# SCH_ESP32_Master_Board_2023-08-22.net
KiCad netlist of a schematic drawn in EasyEDA
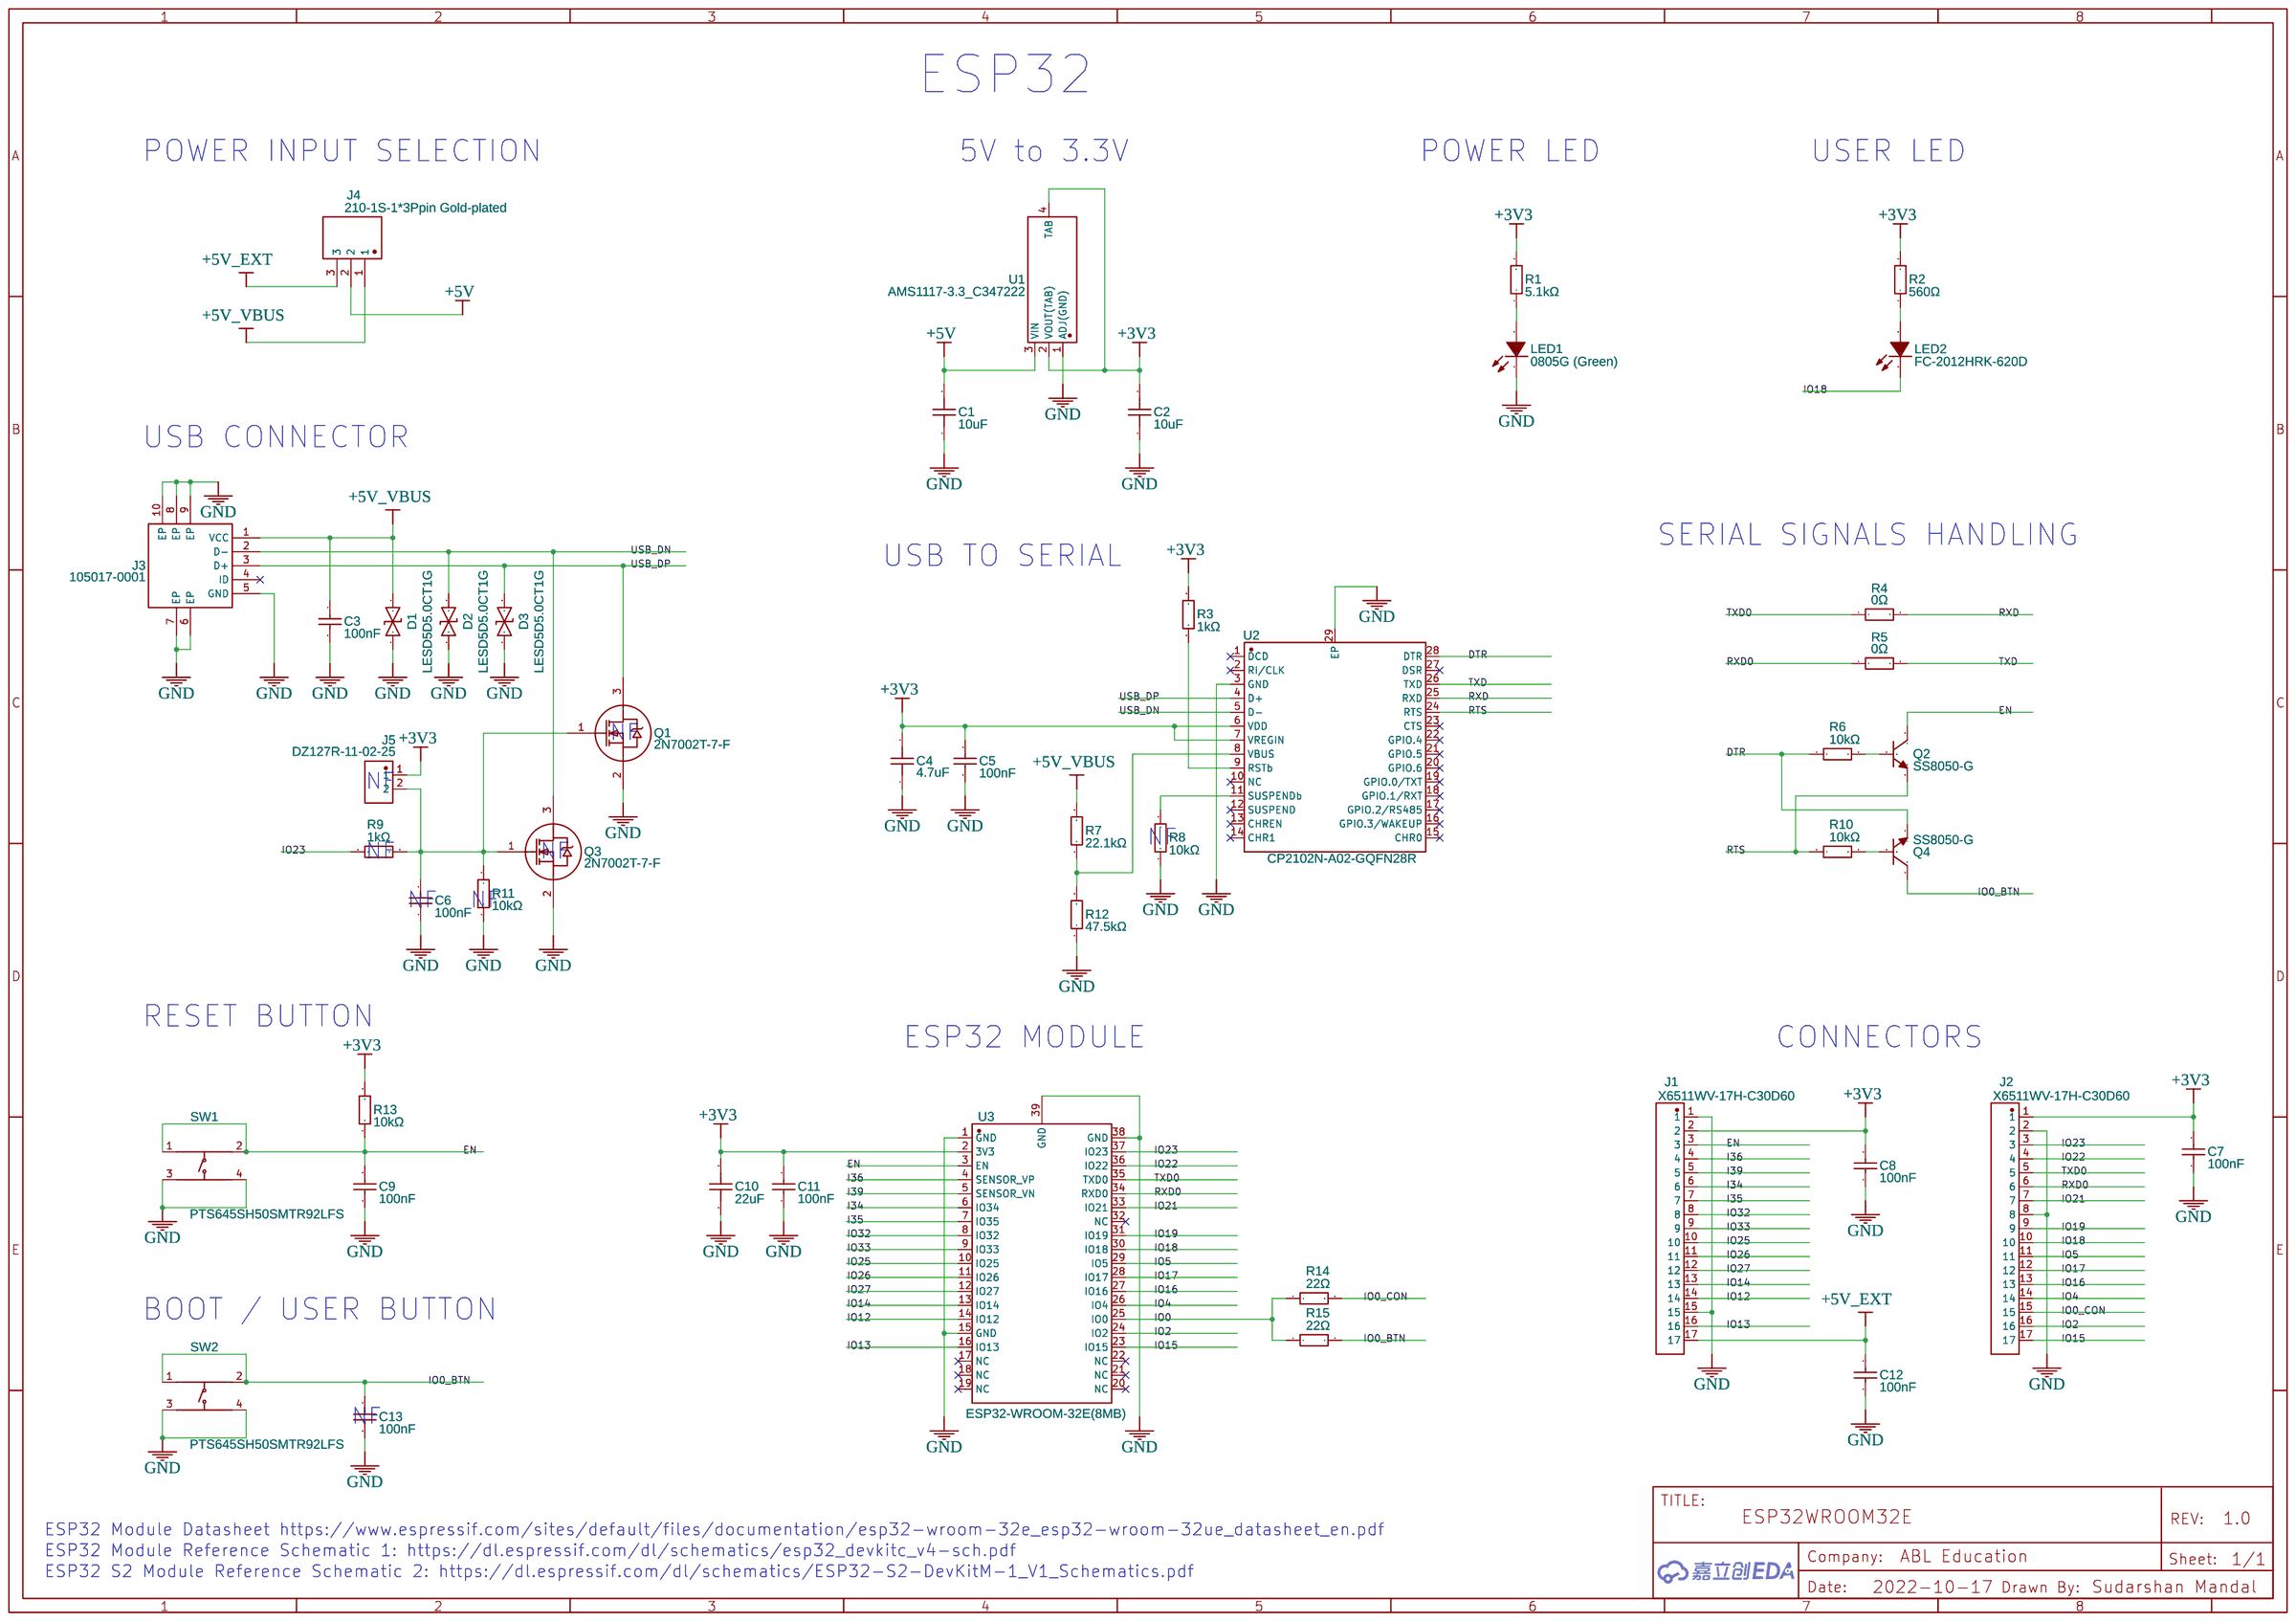
[diagram p0: schematic sheet]

(export (version "E")
  (design (tool "Eeschema 10.0.6"))
  (components
    (comp (ref "C1")
      (value "10uF")
      (fields
        (field (name "Manufacturer Part") "CL05A106MP5NUNC")
        (field (name "Manufacturer") "Samsung Electro-Mechanics")
      )
      (libsource (lib "") (part "CL05A106MP5NUNC_C315248"))
    )
    (comp (ref "C2")
      (value "10uF")
      (fields
        (field (name "Manufacturer Part") "CL05A106MP5NUNC")
        (field (name "Manufacturer") "Samsung Electro-Mechanics")
      )
      (libsource (lib "") (part "CL05A106MP5NUNC_C315248"))
    )
    (comp (ref "C3")
      (value "100nF")
      (fields (field (name "Manufacturer Part") "CL05B104KO5NNNC") (field (name "Manufacturer") "SAMSUNG"))
      (libsource (lib "") (part "CL05B104KO5NNNC"))
    )
    (comp (ref "C4")
      (value "4.7uF")
      (fields
        (field (name "Manufacturer Part") "CL05A475KP5NRNC")
        (field (name "Manufacturer") "Samsung Electro-Mechanics")
      )
      (libsource (lib "") (part "CL05A475KP5NRNC"))
    )
    (comp (ref "C5")
      (value "100nF")
      (fields (field (name "Manufacturer Part") "CL05B104KO5NNNC") (field (name "Manufacturer") "SAMSUNG"))
      (libsource (lib "") (part "CL05B104KO5NNNC"))
    )
    (comp (ref "C6")
      (value "100nF")
      (fields (field (name "Manufacturer Part") "CL05B104KO5NNNC") (field (name "Manufacturer") "SAMSUNG"))
      (libsource (lib "") (part "CL05B104KO5NNNC"))
    )
    (comp (ref "C7")
      (value "100nF")
      (fields (field (name "Manufacturer Part") "CL05B104KO5NNNC") (field (name "Manufacturer") "SAMSUNG"))
      (libsource (lib "") (part "CL05B104KO5NNNC"))
    )
    (comp (ref "C8")
      (value "100nF")
      (fields (field (name "Manufacturer Part") "CL05B104KO5NNNC") (field (name "Manufacturer") "SAMSUNG"))
      (libsource (lib "") (part "CL05B104KO5NNNC"))
    )
    (comp (ref "C9")
      (value "100nF")
      (fields (field (name "Manufacturer Part") "CL05B104KO5NNNC") (field (name "Manufacturer") "SAMSUNG"))
      (libsource (lib "") (part "CL05B104KO5NNNC"))
    )
    (comp (ref "C10")
      (value "22uF")
      (fields
        (field (name "Manufacturer Part") "CL21A226MAYNNNE")
        (field (name "Manufacturer") "Samsung Electro-Mechanics")
      )
      (libsource (lib "") (part "CL21A226MAYNNNE"))
    )
    (comp (ref "C11")
      (value "100nF")
      (fields (field (name "Manufacturer Part") "CL05B104KO5NNNC") (field (name "Manufacturer") "SAMSUNG"))
      (libsource (lib "") (part "CL05B104KO5NNNC"))
    )
    (comp (ref "C12")
      (value "100nF")
      (fields (field (name "Manufacturer Part") "CL05B104KO5NNNC") (field (name "Manufacturer") "SAMSUNG"))
      (libsource (lib "") (part "CL05B104KO5NNNC"))
    )
    (comp (ref "C13")
      (value "100nF")
      (fields (field (name "Manufacturer Part") "CL05B104KO5NNNC") (field (name "Manufacturer") "SAMSUNG"))
      (libsource (lib "") (part "CL05B104KO5NNNC"))
    )
    (comp (ref "D1")
      (value "LESD5D5.0CT1G")
      (fields (field (name "Manufacturer") "Leshan Radio"))
      (libsource (lib "") (part "LESD5D5.0CT1G"))
    )
    (comp (ref "D2")
      (value "LESD5D5.0CT1G")
      (fields (field (name "Manufacturer") "Leshan Radio"))
      (libsource (lib "") (part "LESD5D5.0CT1G"))
    )
    (comp (ref "D3")
      (value "LESD5D5.0CT1G")
      (fields (field (name "Manufacturer") "Leshan Radio"))
      (libsource (lib "") (part "LESD5D5.0CT1G"))
    )
    (comp (ref "J1")
      (value "X6511WV-17H-C30D60")
      (fields (field (name "Manufacturer") "XKB Connectivity"))
      (libsource (lib "") (part "X6511WV-17H-C30D60"))
    )
    (comp (ref "J2")
      (value "X6511WV-17H-C30D60")
      (fields (field (name "Manufacturer") "XKB Connectivity"))
      (libsource (lib "") (part "X6511WV-17H-C30D60"))
    )
    (comp (ref "J3")
      (value "105017-0001")
      (fields (field (name "Manufacturer") "MOLEX"))
      (libsource (lib "") (part "105017-0001"))
    )
    (comp (ref "J4")
      (value "210-1S-1*3Ppin Gold-plated")
      (fields (field (name "Manufacturer") "Ckmtw"))
      (libsource (lib "") (part "210-1S-1*3Ppin Gold-plated"))
    )
    (comp (ref "J5")
      (value "DZ127R-11-02-25")
      (fields (field (name "Manufacturer") "DEALON(德艺隆)"))
      (libsource (lib "") (part "DZ127R-11-02-25"))
    )
    (comp (ref "LED1")
      (value "0805G (Green)")
      (fields (field (name "Manufacturer") "KENTO"))
      (libsource (lib "") (part "0805G (Green)"))
    )
    (comp (ref "LED2")
      (value "FC-2012HRK-620D")
      (fields (field (name "Manufacturer") "NATIONSTAR"))
      (libsource (lib "") (part "FC-2012HRK-620D"))
    )
    (comp (ref "Q1")
      (value "2N7002T-7-F")
      (fields (field (name "Manufacturer") "DIODES"))
      (libsource (lib "") (part "2N7002T-7-F"))
    )
    (comp (ref "Q2")
      (value "SS8050-G")
      (fields (field (name "Manufacturer") "CJ(江苏长电/长晶)"))
      (libsource (lib "") (part "SS8050-G"))
    )
    (comp (ref "Q3")
      (value "2N7002T-7-F")
      (fields (field (name "Manufacturer") "DIODES"))
      (libsource (lib "") (part "2N7002T-7-F"))
    )
    (comp (ref "Q4")
      (value "SS8050-G")
      (fields (field (name "Manufacturer") "CJ(江苏长电/长晶)"))
      (libsource (lib "") (part "SS8050-G_1"))
    )
    (comp (ref "R1")
      (value "5.1kΩ")
      (fields (field (name "Manufacturer Part") "0402WGF5101TCE") (field (name "Manufacturer") "UniOhm"))
      (libsource (lib "") (part "0402WGF5101TCE"))
    )
    (comp (ref "R2")
      (value "560Ω")
      (fields (field (name "Manufacturer Part") "0402WGF5600TCE") (field (name "Manufacturer") "UniOhm"))
      (libsource (lib "") (part "0402WGF5600TCE"))
    )
    (comp (ref "R3")
      (value "1kΩ")
      (fields (field (name "Manufacturer Part") "0402WGF1001TCE") (field (name "Manufacturer") "UniOhm"))
      (libsource (lib "") (part "0402WGF1001TCE"))
    )
    (comp (ref "R4")
      (value "0Ω")
      (fields (field (name "Manufacturer Part") "0402WGF0000TCE") (field (name "Manufacturer") "UniOhm"))
      (libsource (lib "") (part "0402WGF0000TCE"))
    )
    (comp (ref "R5")
      (value "0Ω")
      (fields (field (name "Manufacturer Part") "0402WGF0000TCE") (field (name "Manufacturer") "UniOhm"))
      (libsource (lib "") (part "0402WGF0000TCE"))
    )
    (comp (ref "R6")
      (value "10kΩ")
      (fields (field (name "Manufacturer Part") "0402WGF1002TCE") (field (name "Manufacturer") "UniOhm"))
      (libsource (lib "") (part "0402WGF1002TCE_1"))
    )
    (comp (ref "R7")
      (value "22.1kΩ")
      (fields (field (name "Manufacturer Part") "0402WGF2212TCE") (field (name "Manufacturer") "UniOhm"))
      (libsource (lib "") (part "0402WGF2212TCE"))
    )
    (comp (ref "R8")
      (value "10kΩ")
      (fields (field (name "Manufacturer Part") "0402WGF1002TCE") (field (name "Manufacturer") "UniOhm"))
      (libsource (lib "") (part "0402WGF1002TCE"))
    )
    (comp (ref "R9")
      (value "1kΩ")
      (fields (field (name "Manufacturer Part") "0402WGF1001TCE") (field (name "Manufacturer") "UniOhm"))
      (libsource (lib "") (part "0402WGF1001TCE_1"))
    )
    (comp (ref "R10")
      (value "10kΩ")
      (fields (field (name "Manufacturer Part") "0402WGF1002TCE") (field (name "Manufacturer") "UniOhm"))
      (libsource (lib "") (part "0402WGF1002TCE_1"))
    )
    (comp (ref "R11")
      (value "10kΩ")
      (fields (field (name "Manufacturer Part") "0402WGF1002TCE") (field (name "Manufacturer") "UniOhm"))
      (libsource (lib "") (part "0402WGF1002TCE"))
    )
    (comp (ref "R12")
      (value "47.5kΩ")
      (fields (field (name "Manufacturer Part") "0402WGF4752TCE") (field (name "Manufacturer") "UniOhm"))
      (libsource (lib "") (part "0402WGF4752TCE"))
    )
    (comp (ref "R13")
      (value "10kΩ")
      (fields (field (name "Manufacturer Part") "0402WGF1002TCE") (field (name "Manufacturer") "UniOhm"))
      (libsource (lib "") (part "0402WGF1002TCE"))
    )
    (comp (ref "R14")
      (value "22Ω")
      (fields (field (name "Manufacturer Part") "0402WGF220JTCE") (field (name "Manufacturer") "UniOhm"))
      (libsource (lib "") (part "0402WGF220JTCE"))
    )
    (comp (ref "R15")
      (value "22Ω")
      (fields (field (name "Manufacturer Part") "0402WGF220JTCE") (field (name "Manufacturer") "UniOhm"))
      (libsource (lib "") (part "0402WGF220JTCE"))
    )
    (comp (ref "SW1")
      (value "PTS645SH50SMTR92LFS")
      (fields (field (name "Manufacturer") "C&K"))
      (libsource (lib "") (part "PTS645SH50SMTR92LFS"))
    )
    (comp (ref "SW2")
      (value "PTS645SH50SMTR92LFS")
      (fields (field (name "Manufacturer") "C&K"))
      (libsource (lib "") (part "PTS645SH50SMTR92LFS"))
    )
    (comp (ref "U1")
      (value "AMS1117-3.3_C347222")
      (fields
        (field (name "Manufacturer Part") "AMS1117-3.3")
        (field (name "Manufacturer") "Youtai Semiconductor Co., Ltd.")
      )
      (libsource (lib "") (part "AMS1117-3.3_C347222"))
    )
    (comp (ref "U2")
      (value "CP2102N-A02-GQFN28R")
      (fields (field (name "Manufacturer") "SILICON LABS(芯科)"))
      (libsource (lib "") (part "CP2102N-A02-GQFN28R"))
    )
    (comp (ref "U3")
      (value "ESP32-WROOM-32E(8MB)")
      (fields (field (name "Manufacturer") "Espressif Systems"))
      (libsource (lib "") (part "ESP32-WROOM-32E(8MB)"))
    )
  )
  (nets
    (net (code "1") (name "+3V3") (class "Default")
      (node (ref "C10") (pin "2") (pinfunction "2_2") (pintype "unspecified"))
      (node (ref "C11") (pin "2") (pinfunction "2_2") (pintype "input"))
      (node (ref "C2") (pin "2") (pinfunction "2_2") (pintype "unspecified"))
      (node (ref "C4") (pin "2") (pinfunction "2_2") (pintype "unspecified"))
      (node (ref "C5") (pin "2") (pinfunction "2_2") (pintype "input"))
      (node (ref "C7") (pin "2") (pinfunction "2_2") (pintype "input"))
      (node (ref "C8") (pin "2") (pinfunction "2_2") (pintype "input"))
      (node (ref "J1") (pin "2") (pinfunction "2_2") (pintype "unspecified"))
      (node (ref "J2") (pin "1") (pinfunction "1_1") (pintype "unspecified"))
      (node (ref "J5") (pin "1") (pinfunction "1_1") (pintype "unspecified"))
      (node (ref "R1") (pin "2") (pinfunction "2_2") (pintype "input"))
      (node (ref "R13") (pin "2") (pinfunction "2_2") (pintype "input"))
      (node (ref "R2") (pin "2") (pinfunction "2_2") (pintype "input"))
      (node (ref "R3") (pin "2") (pinfunction "2_2") (pintype "input"))
      (node (ref "U1") (pin "2") (pinfunction "VOUT(TAB)_2") (pintype "unspecified"))
      (node (ref "U1") (pin "4") (pinfunction "TAB_4") (pintype "unspecified"))
      (node (ref "U2") (pin "6") (pinfunction "VDD_6") (pintype "unspecified"))
      (node (ref "U2") (pin "7") (pinfunction "VREGIN_7") (pintype "unspecified"))
      (node (ref "U3") (pin "2") (pinfunction "3V3_2") (pintype "unspecified"))
    )
    (net (code "2") (name "+5V") (class "Default")
      (node (ref "C1") (pin "2") (pinfunction "2_2") (pintype "unspecified"))
      (node (ref "J4") (pin "2") (pinfunction "2_2") (pintype "unspecified"))
      (node (ref "U1") (pin "3") (pinfunction "VIN_3") (pintype "unspecified"))
    )
    (net (code "3") (name "+5V_EXT") (class "Default")
      (node (ref "C12") (pin "2") (pinfunction "2_2") (pintype "input"))
      (node (ref "J1") (pin "17") (pinfunction "17_17") (pintype "unspecified"))
      (node (ref "J4") (pin "3") (pinfunction "3_3") (pintype "unspecified"))
    )
    (net (code "4") (name "+5V_VBUS") (class "Default")
      (node (ref "C3") (pin "2") (pinfunction "2_2") (pintype "input"))
      (node (ref "D1") (pin "2") (pinfunction "2_2") (pintype "unspecified"))
      (node (ref "J3") (pin "1") (pinfunction "VCC_1") (pintype "unspecified"))
      (node (ref "J4") (pin "1") (pinfunction "1_1") (pintype "unspecified"))
      (node (ref "R7") (pin "2") (pinfunction "2_2") (pintype "input"))
    )
    (net (code "5") (name "/DTR") (class "Default")
      (node (ref "Q4") (pin "2") (pinfunction "E_2") (pintype "input"))
      (node (ref "R6") (pin "1") (pinfunction "1_1") (pintype "input"))
      (node (ref "U2") (pin "28") (pinfunction "DTR_28") (pintype "unspecified"))
    )
    (net (code "6") (name "/EN") (class "Default")
      (node (ref "C9") (pin "2") (pinfunction "2_2") (pintype "input"))
      (node (ref "J1") (pin "3") (pinfunction "3_3") (pintype "unspecified"))
      (node (ref "Q2") (pin "3") (pinfunction "C_3") (pintype "input"))
      (node (ref "R13") (pin "1") (pinfunction "1_1") (pintype "input"))
      (node (ref "SW1") (pin "1") (pinfunction "1_1") (pintype "unspecified"))
      (node (ref "SW1") (pin "2") (pinfunction "2_2") (pintype "unspecified"))
      (node (ref "U3") (pin "3") (pinfunction "EN_3") (pintype "unspecified"))
    )
    (net (code "7") (name "/I34") (class "Default")
      (node (ref "J1") (pin "6") (pinfunction "6_6") (pintype "unspecified"))
      (node (ref "U3") (pin "6") (pinfunction "IO34_6") (pintype "unspecified"))
    )
    (net (code "8") (name "/I35") (class "Default")
      (node (ref "J1") (pin "7") (pinfunction "7_7") (pintype "unspecified"))
      (node (ref "U3") (pin "7") (pinfunction "IO35_7") (pintype "unspecified"))
    )
    (net (code "9") (name "/I36") (class "Default")
      (node (ref "J1") (pin "4") (pinfunction "4_4") (pintype "unspecified"))
      (node (ref "U3") (pin "4") (pinfunction "SENSOR_VP_4") (pintype "unspecified"))
    )
    (net (code "10") (name "/I39") (class "Default")
      (node (ref "J1") (pin "5") (pinfunction "5_5") (pintype "unspecified"))
      (node (ref "U3") (pin "5") (pinfunction "SENSOR_VN_5") (pintype "unspecified"))
    )
    (net (code "11") (name "/IO0") (class "Default")
      (node (ref "R14") (pin "1") (pinfunction "1_1") (pintype "input"))
      (node (ref "R15") (pin "1") (pinfunction "1_1") (pintype "input"))
      (node (ref "U3") (pin "25") (pinfunction "IO0_25") (pintype "unspecified"))
    )
    (net (code "12") (name "/IO0_BTN") (class "Default")
      (node (ref "C13") (pin "2") (pinfunction "2_2") (pintype "input"))
      (node (ref "Q4") (pin "3") (pinfunction "C_3") (pintype "input"))
      (node (ref "R15") (pin "2") (pinfunction "2_2") (pintype "input"))
      (node (ref "SW2") (pin "1") (pinfunction "1_1") (pintype "unspecified"))
      (node (ref "SW2") (pin "2") (pinfunction "2_2") (pintype "unspecified"))
    )
    (net (code "13") (name "/IO0_CON") (class "Default")
      (node (ref "J2") (pin "15") (pinfunction "15_15") (pintype "unspecified"))
      (node (ref "R14") (pin "2") (pinfunction "2_2") (pintype "input"))
    )
    (net (code "14") (name "/IO2") (class "Default")
      (node (ref "J2") (pin "16") (pinfunction "16_16") (pintype "unspecified"))
      (node (ref "U3") (pin "24") (pinfunction "IO2_24") (pintype "unspecified"))
    )
    (net (code "15") (name "/IO4") (class "Default")
      (node (ref "J2") (pin "14") (pinfunction "14_14") (pintype "unspecified"))
      (node (ref "U3") (pin "26") (pinfunction "IO4_26") (pintype "unspecified"))
    )
    (net (code "16") (name "/IO5") (class "Default")
      (node (ref "J2") (pin "11") (pinfunction "11_11") (pintype "unspecified"))
      (node (ref "U3") (pin "29") (pinfunction "IO5_29") (pintype "unspecified"))
    )
    (net (code "17") (name "/IO12") (class "Default")
      (node (ref "J1") (pin "14") (pinfunction "14_14") (pintype "unspecified"))
      (node (ref "U3") (pin "14") (pinfunction "IO12_14") (pintype "unspecified"))
    )
    (net (code "18") (name "/IO13") (class "Default")
      (node (ref "J1") (pin "16") (pinfunction "16_16") (pintype "unspecified"))
      (node (ref "U3") (pin "16") (pinfunction "IO13_16") (pintype "unspecified"))
    )
    (net (code "19") (name "/IO14") (class "Default")
      (node (ref "J1") (pin "13") (pinfunction "13_13") (pintype "unspecified"))
      (node (ref "U3") (pin "13") (pinfunction "IO14_13") (pintype "unspecified"))
    )
    (net (code "20") (name "/IO15") (class "Default")
      (node (ref "J2") (pin "17") (pinfunction "17_17") (pintype "unspecified"))
      (node (ref "U3") (pin "23") (pinfunction "IO15_23") (pintype "unspecified"))
    )
    (net (code "21") (name "/IO16") (class "Default")
      (node (ref "J2") (pin "13") (pinfunction "13_13") (pintype "unspecified"))
      (node (ref "U3") (pin "27") (pinfunction "IO16_27") (pintype "unspecified"))
    )
    (net (code "22") (name "/IO17") (class "Default")
      (node (ref "J2") (pin "12") (pinfunction "12_12") (pintype "unspecified"))
      (node (ref "U3") (pin "28") (pinfunction "IO17_28") (pintype "unspecified"))
    )
    (net (code "23") (name "/IO18") (class "Default")
      (node (ref "J2") (pin "10") (pinfunction "10_10") (pintype "unspecified"))
      (node (ref "LED2") (pin "1") (pinfunction "-_1") (pintype "unspecified"))
      (node (ref "U3") (pin "30") (pinfunction "IO18_30") (pintype "unspecified"))
    )
    (net (code "24") (name "/IO19") (class "Default")
      (node (ref "J2") (pin "9") (pinfunction "9_9") (pintype "unspecified"))
      (node (ref "U3") (pin "31") (pinfunction "IO19_31") (pintype "unspecified"))
    )
    (net (code "25") (name "/IO21") (class "Default")
      (node (ref "J2") (pin "7") (pinfunction "7_7") (pintype "unspecified"))
      (node (ref "U3") (pin "33") (pinfunction "IO21_33") (pintype "unspecified"))
    )
    (net (code "26") (name "/IO22") (class "Default")
      (node (ref "J2") (pin "4") (pinfunction "4_4") (pintype "unspecified"))
      (node (ref "U3") (pin "36") (pinfunction "IO22_36") (pintype "unspecified"))
    )
    (net (code "27") (name "/IO23") (class "Default")
      (node (ref "J2") (pin "3") (pinfunction "3_3") (pintype "unspecified"))
      (node (ref "R9") (pin "2") (pinfunction "2_2") (pintype "input"))
      (node (ref "U3") (pin "37") (pinfunction "IO23_37") (pintype "unspecified"))
    )
    (net (code "28") (name "/IO25") (class "Default")
      (node (ref "J1") (pin "10") (pinfunction "10_10") (pintype "unspecified"))
      (node (ref "U3") (pin "10") (pinfunction "IO25_10") (pintype "unspecified"))
    )
    (net (code "29") (name "/IO26") (class "Default")
      (node (ref "J1") (pin "11") (pinfunction "11_11") (pintype "unspecified"))
      (node (ref "U3") (pin "11") (pinfunction "IO26_11") (pintype "unspecified"))
    )
    (net (code "30") (name "/IO27") (class "Default")
      (node (ref "J1") (pin "12") (pinfunction "12_12") (pintype "unspecified"))
      (node (ref "U3") (pin "12") (pinfunction "IO27_12") (pintype "unspecified"))
    )
    (net (code "31") (name "/IO32") (class "Default")
      (node (ref "J1") (pin "8") (pinfunction "8_8") (pintype "unspecified"))
      (node (ref "U3") (pin "8") (pinfunction "IO32_8") (pintype "unspecified"))
    )
    (net (code "32") (name "/IO33") (class "Default")
      (node (ref "J1") (pin "9") (pinfunction "9_9") (pintype "unspecified"))
      (node (ref "U3") (pin "9") (pinfunction "IO33_9") (pintype "unspecified"))
    )
    (net (code "33") (name "/RTS") (class "Default")
      (node (ref "Q2") (pin "2") (pinfunction "E_2") (pintype "input"))
      (node (ref "R10") (pin "1") (pinfunction "1_1") (pintype "input"))
      (node (ref "U2") (pin "24") (pinfunction "RTS_24") (pintype "unspecified"))
    )
    (net (code "34") (name "/RXD") (class "Default")
      (node (ref "R4") (pin "2") (pinfunction "2_2") (pintype "input"))
      (node (ref "U2") (pin "25") (pinfunction "RXD_25") (pintype "unspecified"))
    )
    (net (code "35") (name "/RXD0") (class "Default")
      (node (ref "J2") (pin "6") (pinfunction "6_6") (pintype "unspecified"))
      (node (ref "R5") (pin "1") (pinfunction "1_1") (pintype "input"))
      (node (ref "U3") (pin "34") (pinfunction "RXD0_34") (pintype "unspecified"))
    )
    (net (code "36") (name "/TXD") (class "Default")
      (node (ref "R5") (pin "2") (pinfunction "2_2") (pintype "input"))
      (node (ref "U2") (pin "26") (pinfunction "TXD_26") (pintype "unspecified"))
    )
    (net (code "37") (name "/TXD0") (class "Default")
      (node (ref "J2") (pin "5") (pinfunction "5_5") (pintype "unspecified"))
      (node (ref "R4") (pin "1") (pinfunction "1_1") (pintype "input"))
      (node (ref "U3") (pin "35") (pinfunction "TXD0_35") (pintype "unspecified"))
    )
    (net (code "38") (name "/USB_DN") (class "Default")
      (node (ref "D2") (pin "2") (pinfunction "2_2") (pintype "unspecified"))
      (node (ref "J3") (pin "2") (pinfunction "D-_2") (pintype "unspecified"))
      (node (ref "Q3") (pin "3") (pinfunction "D_3") (pintype "unspecified"))
      (node (ref "U2") (pin "5") (pinfunction "D-_5") (pintype "unspecified"))
    )
    (net (code "39") (name "/USB_DP") (class "Default")
      (node (ref "D3") (pin "2") (pinfunction "2_2") (pintype "unspecified"))
      (node (ref "J3") (pin "3") (pinfunction "D+_3") (pintype "unspecified"))
      (node (ref "Q1") (pin "3") (pinfunction "D_3") (pintype "unspecified"))
      (node (ref "U2") (pin "4") (pinfunction "D+_4") (pintype "unspecified"))
    )
    (net (code "40") (name "GND") (class "Default")
      (node (ref "C1") (pin "1") (pinfunction "1_1") (pintype "unspecified"))
      (node (ref "C10") (pin "1") (pinfunction "1_1") (pintype "unspecified"))
      (node (ref "C11") (pin "1") (pinfunction "1_1") (pintype "input"))
      (node (ref "C12") (pin "1") (pinfunction "1_1") (pintype "input"))
      (node (ref "C13") (pin "1") (pinfunction "1_1") (pintype "input"))
      (node (ref "C2") (pin "1") (pinfunction "1_1") (pintype "unspecified"))
      (node (ref "C3") (pin "1") (pinfunction "1_1") (pintype "input"))
      (node (ref "C4") (pin "1") (pinfunction "1_1") (pintype "unspecified"))
      (node (ref "C5") (pin "1") (pinfunction "1_1") (pintype "input"))
      (node (ref "C6") (pin "1") (pinfunction "1_1") (pintype "input"))
      (node (ref "C7") (pin "1") (pinfunction "1_1") (pintype "input"))
      (node (ref "C8") (pin "1") (pinfunction "1_1") (pintype "input"))
      (node (ref "C9") (pin "1") (pinfunction "1_1") (pintype "input"))
      (node (ref "D1") (pin "1") (pinfunction "1_1") (pintype "unspecified"))
      (node (ref "D2") (pin "1") (pinfunction "1_1") (pintype "unspecified"))
      (node (ref "D3") (pin "1") (pinfunction "1_1") (pintype "unspecified"))
      (node (ref "J1") (pin "1") (pinfunction "1_1") (pintype "unspecified"))
      (node (ref "J1") (pin "15") (pinfunction "15_15") (pintype "unspecified"))
      (node (ref "J2") (pin "2") (pinfunction "2_2") (pintype "unspecified"))
      (node (ref "J2") (pin "8") (pinfunction "8_8") (pintype "unspecified"))
      (node (ref "J3") (pin "10") (pinfunction "EP_10") (pintype "unspecified"))
      (node (ref "J3") (pin "5") (pinfunction "GND_5") (pintype "unspecified"))
      (node (ref "J3") (pin "6") (pinfunction "EP_6") (pintype "unspecified"))
      (node (ref "J3") (pin "7") (pinfunction "EP_7") (pintype "unspecified"))
      (node (ref "J3") (pin "8") (pinfunction "EP_8") (pintype "unspecified"))
      (node (ref "J3") (pin "9") (pinfunction "EP_9") (pintype "unspecified"))
      (node (ref "LED1") (pin "1") (pinfunction "K_1") (pintype "unspecified"))
      (node (ref "Q1") (pin "2") (pinfunction "S_2") (pintype "unspecified"))
      (node (ref "Q3") (pin "2") (pinfunction "S_2") (pintype "unspecified"))
      (node (ref "R11") (pin "1") (pinfunction "1_1") (pintype "input"))
      (node (ref "R12") (pin "1") (pinfunction "1_1") (pintype "input"))
      (node (ref "R8") (pin "1") (pinfunction "1_1") (pintype "input"))
      (node (ref "SW1") (pin "3") (pinfunction "3_3") (pintype "unspecified"))
      (node (ref "SW1") (pin "4") (pinfunction "4_4") (pintype "unspecified"))
      (node (ref "SW2") (pin "3") (pinfunction "3_3") (pintype "unspecified"))
      (node (ref "SW2") (pin "4") (pinfunction "4_4") (pintype "unspecified"))
      (node (ref "U1") (pin "1") (pinfunction "ADJ(GND)_1") (pintype "unspecified"))
      (node (ref "U2") (pin "29") (pinfunction "EP_29") (pintype "unspecified"))
      (node (ref "U2") (pin "3") (pinfunction "GND_3") (pintype "unspecified"))
      (node (ref "U3") (pin "1") (pinfunction "GND_1") (pintype "unspecified"))
      (node (ref "U3") (pin "15") (pinfunction "GND_15") (pintype "unspecified"))
      (node (ref "U3") (pin "38") (pinfunction "GND_38") (pintype "unspecified"))
      (node (ref "U3") (pin "39") (pinfunction "GND_39") (pintype "unspecified"))
    )
    (net (code "41") (name "Net-(LED1-A)") (class "Default")
      (node (ref "LED1") (pin "2") (pinfunction "A_2") (pintype "unspecified"))
      (node (ref "R1") (pin "1") (pinfunction "1_1") (pintype "input"))
    )
    (net (code "42") (name "Net-(LED2-+)") (class "Default")
      (node (ref "LED2") (pin "2") (pinfunction "+_2") (pintype "unspecified"))
      (node (ref "R2") (pin "1") (pinfunction "1_1") (pintype "input"))
    )
    (net (code "43") (name "Net-(Q1-G)") (class "Default")
      (node (ref "C6") (pin "2") (pinfunction "2_2") (pintype "input"))
      (node (ref "J5") (pin "2") (pinfunction "2_2") (pintype "unspecified"))
      (node (ref "Q1") (pin "1") (pinfunction "G_1") (pintype "unspecified"))
      (node (ref "Q3") (pin "1") (pinfunction "G_1") (pintype "unspecified"))
      (node (ref "R11") (pin "2") (pinfunction "2_2") (pintype "input"))
      (node (ref "R9") (pin "1") (pinfunction "1_1") (pintype "input"))
    )
    (net (code "44") (name "Net-(Q2-B)") (class "Default")
      (node (ref "Q2") (pin "1") (pinfunction "B_1") (pintype "input"))
      (node (ref "R6") (pin "2") (pinfunction "2_2") (pintype "input"))
    )
    (net (code "45") (name "Net-(Q4-B)") (class "Default")
      (node (ref "Q4") (pin "1") (pinfunction "B_1") (pintype "input"))
      (node (ref "R10") (pin "2") (pinfunction "2_2") (pintype "input"))
    )
    (net (code "46") (name "Net-(U2-RSTb)") (class "Default")
      (node (ref "R3") (pin "1") (pinfunction "1_1") (pintype "input"))
      (node (ref "U2") (pin "9") (pinfunction "RSTb_9") (pintype "unspecified"))
    )
    (net (code "47") (name "Net-(U2-SUSPENDb)") (class "Default")
      (node (ref "R8") (pin "2") (pinfunction "2_2") (pintype "input"))
      (node (ref "U2") (pin "11") (pinfunction "SUSPENDb_11") (pintype "unspecified"))
    )
    (net (code "48") (name "Net-(U2-VBUS)") (class "Default")
      (node (ref "R12") (pin "2") (pinfunction "2_2") (pintype "input"))
      (node (ref "R7") (pin "1") (pinfunction "1_1") (pintype "input"))
      (node (ref "U2") (pin "8") (pinfunction "VBUS_8") (pintype "unspecified"))
    )
    (net (code "49") (name "unconnected-(J3-ID-Pad4)") (class "Default")
      (node (ref "J3") (pin "4") (pinfunction "ID_4") (pintype "unspecified+no_connect"))
    )
    (net (code "50") (name "unconnected-(U2-CHR0-Pad15)") (class "Default")
      (node (ref "U2") (pin "15") (pinfunction "CHR0_15") (pintype "unspecified+no_connect"))
    )
    (net (code "51") (name "unconnected-(U2-CHR1-Pad14)") (class "Default")
      (node (ref "U2") (pin "14") (pinfunction "CHR1_14") (pintype "unspecified+no_connect"))
    )
    (net (code "52") (name "unconnected-(U2-CHREN-Pad13)") (class "Default")
      (node (ref "U2") (pin "13") (pinfunction "CHREN_13") (pintype "unspecified+no_connect"))
    )
    (net (code "53") (name "unconnected-(U2-CTS-Pad23)") (class "Default")
      (node (ref "U2") (pin "23") (pinfunction "CTS_23") (pintype "unspecified+no_connect"))
    )
    (net (code "54") (name "unconnected-(U2-DCD-Pad1)") (class "Default")
      (node (ref "U2") (pin "1") (pinfunction "DCD_1") (pintype "unspecified+no_connect"))
    )
    (net (code "55") (name "unconnected-(U2-DSR-Pad27)") (class "Default")
      (node (ref "U2") (pin "27") (pinfunction "DSR_27") (pintype "unspecified+no_connect"))
    )
    (net (code "56") (name "unconnected-(U2-GPIO.0{slash}TXT-Pad19)") (class "Default")
      (node (ref "U2") (pin "19") (pinfunction "GPIO.0/TXT_19") (pintype "unspecified+no_connect"))
    )
    (net (code "57") (name "unconnected-(U2-GPIO.1{slash}RXT-Pad18)") (class "Default")
      (node (ref "U2") (pin "18") (pinfunction "GPIO.1/RXT_18") (pintype "unspecified+no_connect"))
    )
    (net (code "58") (name "unconnected-(U2-GPIO.2{slash}RS485-Pad17)") (class "Default")
      (node (ref "U2") (pin "17") (pinfunction "GPIO.2/RS485_17") (pintype "unspecified+no_connect"))
    )
    (net (code "59") (name "unconnected-(U2-GPIO.3{slash}WAKEUP-Pad16)") (class "Default")
      (node (ref "U2") (pin "16") (pinfunction "GPIO.3/WAKEUP_16") (pintype "unspecified+no_connect"))
    )
    (net (code "60") (name "unconnected-(U2-GPIO.4-Pad22)") (class "Default")
      (node (ref "U2") (pin "22") (pinfunction "GPIO.4_22") (pintype "unspecified+no_connect"))
    )
    (net (code "61") (name "unconnected-(U2-GPIO.5-Pad21)") (class "Default")
      (node (ref "U2") (pin "21") (pinfunction "GPIO.5_21") (pintype "unspecified+no_connect"))
    )
    (net (code "62") (name "unconnected-(U2-GPIO.6-Pad20)") (class "Default")
      (node (ref "U2") (pin "20") (pinfunction "GPIO.6_20") (pintype "unspecified+no_connect"))
    )
    (net (code "63") (name "unconnected-(U2-NC-Pad10)") (class "Default")
      (node (ref "U2") (pin "10") (pinfunction "NC_10") (pintype "unspecified+no_connect"))
    )
    (net (code "64") (name "unconnected-(U2-RI{slash}CLK-Pad2)") (class "Default")
      (node (ref "U2") (pin "2") (pinfunction "RI/CLK_2") (pintype "unspecified+no_connect"))
    )
    (net (code "65") (name "unconnected-(U2-SUSPEND-Pad12)") (class "Default")
      (node (ref "U2") (pin "12") (pinfunction "SUSPEND_12") (pintype "unspecified+no_connect"))
    )
    (net (code "66") (name "unconnected-(U3-NC-Pad17)") (class "Default")
      (node (ref "U3") (pin "17") (pinfunction "NC_17") (pintype "unspecified+no_connect"))
    )
    (net (code "67") (name "unconnected-(U3-NC-Pad18)") (class "Default")
      (node (ref "U3") (pin "18") (pinfunction "NC_18") (pintype "unspecified+no_connect"))
    )
    (net (code "68") (name "unconnected-(U3-NC-Pad19)") (class "Default")
      (node (ref "U3") (pin "19") (pinfunction "NC_19") (pintype "unspecified+no_connect"))
    )
    (net (code "69") (name "unconnected-(U3-NC-Pad20)") (class "Default")
      (node (ref "U3") (pin "20") (pinfunction "NC_20") (pintype "unspecified+no_connect"))
    )
    (net (code "70") (name "unconnected-(U3-NC-Pad21)") (class "Default")
      (node (ref "U3") (pin "21") (pinfunction "NC_21") (pintype "unspecified+no_connect"))
    )
    (net (code "71") (name "unconnected-(U3-NC-Pad22)") (class "Default")
      (node (ref "U3") (pin "22") (pinfunction "NC_22") (pintype "unspecified+no_connect"))
    )
    (net (code "72") (name "unconnected-(U3-NC-Pad32)") (class "Default")
      (node (ref "U3") (pin "32") (pinfunction "NC_32") (pintype "unspecified+no_connect"))
    )
  )
)
